# POWER.net
KiCad netlist of a schematic drawn in Altium Designer
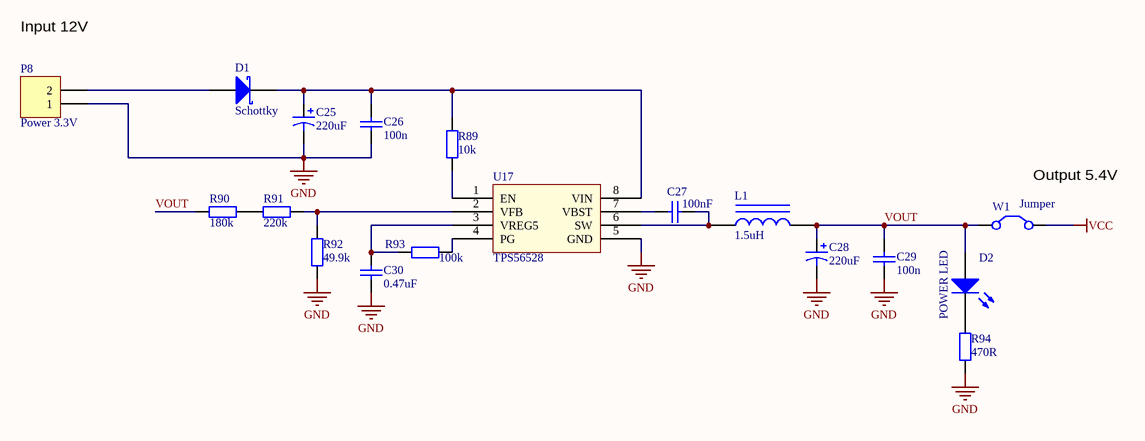
[diagram p0: POWER.SchDoc]

(export (version "E")
  (design (tool "Eeschema 10.0.6"))
  (components
    (comp (ref "C25")
      (value "220uF")
      (footprint "SMD CAPACITOR 220uF")
      (description "Capacitor")
      (fields (field (name "PUBLISHER") "Altium Limited"))
      (libsource (lib "Miscellaneous Devices") (part "Cap Pol1"))
    )
    (comp (ref "C26")
      (value "100n")
      (footprint "1608[0603]")
      (description "Capacitor")
      (fields (field (name "PUBLISHER") "Altium Limited"))
      (libsource (lib "Miscellaneous Devices") (part "Cap"))
    )
    (comp (ref "C27")
      (value "100nF")
      (footprint "1608[0603]")
      (description "Capacitor")
      (fields (field (name "PUBLISHER") "Altium Limited"))
      (libsource (lib "Miscellaneous Devices") (part "Cap"))
    )
    (comp (ref "C28")
      (value "220uF")
      (footprint "SMD CAPACITOR 220uF")
      (description "Capacitor")
      (fields (field (name "PUBLISHER") "Altium Limited"))
      (libsource (lib "Miscellaneous Devices") (part "Cap Pol1"))
    )
    (comp (ref "C29")
      (value "100n")
      (footprint "1608[0603]")
      (description "Capacitor")
      (fields (field (name "PUBLISHER") "Altium Limited"))
      (libsource (lib "Miscellaneous Devices") (part "Cap"))
    )
    (comp (ref "C30")
      (value "0.47uF")
      (footprint "1608[0603]")
      (description "Capacitor")
      (fields (field (name "PUBLISHER") "Altium Limited"))
      (libsource (lib "Miscellaneous Devices") (part "Cap"))
    )
    (comp (ref "D1")
      (value "Schottky")
      (footprint "SMB")
      (description "Schottky Diode")
      (fields (field (name "PUBLISHER") "Altium Limited"))
      (libsource (lib "Miscellaneous Devices") (part "D Schottky"))
    )
    (comp (ref "D2")
      (value "POWER LED")
      (footprint "LED-1")
      (description "Typical INFRARED GaAs LED")
      (fields (field (name "PUBLISHER") "Altium Limited"))
      (libsource (lib "Miscellaneous Devices") (part "LED0"))
    )
    (comp (ref "L1")
      (value "1.5uH")
      (footprint "LukaLIBRARY:Inductor")
      (description "Magnetic-Core Inductor")
      (fields (field (name "PUBLISHER") "Altium Limited"))
      (libsource (lib "Miscellaneous Devices") (part "Inductor Iron"))
    )
    (comp (ref "P8")
      (value "Power 3.3V")
      (footprint "Block2 - 3.81")
      (description "Header, 2-Pin")
      (fields (field (name "PUBLISHER") "Altium Limited"))
      (libsource (lib "Miscellaneous Connectors") (part "Header 2"))
    )
    (comp (ref "R89")
      (value "10k")
      (footprint "1608[0603]")
      (description "Resistor")
      (fields (field (name "PUBLISHER") "Altium Limited"))
      (libsource (lib "Miscellaneous Devices") (part "Res2"))
    )
    (comp (ref "R90")
      (value "180k")
      (footprint "6-0805_L")
      (description "Resistor")
      (fields (field (name "PUBLISHER") "Altium Limited"))
      (libsource (lib "") (part "Res2_1"))
    )
    (comp (ref "R91")
      (value "220k")
      (footprint "6-0805_L")
      (description "Resistor")
      (fields (field (name "PUBLISHER") "Altium Limited"))
      (libsource (lib "") (part "Res2_1"))
    )
    (comp (ref "R92")
      (value "49.9k")
      (footprint "1608[0603]")
      (description "Resistor")
      (fields (field (name "PUBLISHER") "Altium Limited"))
      (libsource (lib "Miscellaneous Devices") (part "Res2"))
    )
    (comp (ref "R93")
      (value "100k")
      (footprint "1608[0603]")
      (description "Resistor")
      (fields (field (name "PUBLISHER") "Altium Limited"))
      (libsource (lib "") (part "Res2_1"))
    )
    (comp (ref "R94")
      (value "470R")
      (footprint "1608[0603]")
      (description "Resistor")
      (fields (field (name "PUBLISHER") "Altium Limited"))
      (libsource (lib "Miscellaneous Devices") (part "Res2"))
    )
    (comp (ref "U17")
      (value "TPS56528")
      (footprint "TPS56528")
      (description "Step-Down Converter 5A 4.5V-18V")
      (libsource (lib "LP_Lib") (part "TPS56528"))
    )
    (comp (ref "W1")
      (value "Jumper")
      (footprint "HDR1X2")
      (description "Jumper Wire")
      (fields (field (name "PUBLISHER") "Altium Limited"))
      (libsource (lib "Miscellaneous Devices") (part "Jumper"))
    )
  )
  (nets
    (net (code "1") (name "/VOUT") (class "Default")
      (node (ref "C28") (pin "1") (pinfunction "1_1") (pintype "passive"))
      (node (ref "C29") (pin "1") (pinfunction "1_1") (pintype "passive"))
      (node (ref "D2") (pin "1") (pinfunction "A_1") (pintype "passive"))
      (node (ref "L1") (pin "2") (pinfunction "2_2") (pintype "passive"))
      (node (ref "R90") (pin "2") (pinfunction "2_2") (pintype "passive"))
      (node (ref "W1") (pin "1") (pinfunction "C1_1") (pintype "passive"))
    )
    (net (code "2") (name "GND") (class "Default")
      (node (ref "C25") (pin "2") (pinfunction "2_2") (pintype "passive"))
      (node (ref "C26") (pin "2") (pinfunction "2_2") (pintype "passive"))
      (node (ref "C28") (pin "2") (pinfunction "2_2") (pintype "passive"))
      (node (ref "C29") (pin "2") (pinfunction "2_2") (pintype "passive"))
      (node (ref "C30") (pin "2") (pinfunction "2_2") (pintype "passive"))
      (node (ref "P8") (pin "1") (pinfunction "1_1") (pintype "passive"))
      (node (ref "R92") (pin "1") (pinfunction "1_1") (pintype "passive"))
      (node (ref "R94") (pin "1") (pinfunction "1_1") (pintype "passive"))
      (node (ref "U17") (pin "5") (pinfunction "GND_5") (pintype "passive"))
    )
    (net (code "3") (name "Net-(D1-A)") (class "Default")
      (node (ref "D1") (pin "1") (pinfunction "A_1") (pintype "passive"))
      (node (ref "P8") (pin "2") (pinfunction "2_2") (pintype "passive"))
    )
    (net (code "4") (name "Net-(D1-K)") (class "Default")
      (node (ref "C25") (pin "1") (pinfunction "1_1") (pintype "passive"))
      (node (ref "C26") (pin "1") (pinfunction "1_1") (pintype "passive"))
      (node (ref "D1") (pin "2") (pinfunction "K_2") (pintype "passive"))
      (node (ref "R89") (pin "2") (pinfunction "2_2") (pintype "passive"))
      (node (ref "U17") (pin "8") (pinfunction "VIN_8") (pintype "passive"))
    )
    (net (code "5") (name "Net-(D2-K)") (class "Default")
      (node (ref "D2") (pin "2") (pinfunction "K_2") (pintype "passive"))
      (node (ref "R94") (pin "2") (pinfunction "2_2") (pintype "passive"))
    )
    (net (code "6") (name "Net-(R90-Pad1)") (class "Default")
      (node (ref "R90") (pin "1") (pinfunction "1_1") (pintype "passive"))
      (node (ref "R91") (pin "2") (pinfunction "2_2") (pintype "passive"))
    )
    (net (code "7") (name "Net-(U17-EN)") (class "Default")
      (node (ref "R89") (pin "1") (pinfunction "1_1") (pintype "passive"))
      (node (ref "U17") (pin "1") (pinfunction "EN_1") (pintype "passive"))
    )
    (net (code "8") (name "Net-(U17-PG)") (class "Default")
      (node (ref "R93") (pin "1") (pinfunction "1_1") (pintype "passive"))
      (node (ref "U17") (pin "4") (pinfunction "PG_4") (pintype "passive"))
    )
    (net (code "9") (name "Net-(U17-SW)") (class "Default")
      (node (ref "C27") (pin "2") (pinfunction "2_2") (pintype "passive"))
      (node (ref "L1") (pin "1") (pinfunction "1_1") (pintype "passive"))
      (node (ref "U17") (pin "6") (pinfunction "SW_6") (pintype "passive"))
    )
    (net (code "10") (name "Net-(U17-VBST)") (class "Default")
      (node (ref "C27") (pin "1") (pinfunction "1_1") (pintype "passive"))
      (node (ref "U17") (pin "7") (pinfunction "VBST_7") (pintype "passive"))
    )
    (net (code "11") (name "Net-(U17-VFB)") (class "Default")
      (node (ref "R91") (pin "1") (pinfunction "1_1") (pintype "passive"))
      (node (ref "R92") (pin "2") (pinfunction "2_2") (pintype "passive"))
      (node (ref "U17") (pin "2") (pinfunction "VFB_2") (pintype "passive"))
    )
    (net (code "12") (name "Net-(U17-VREG5)") (class "Default")
      (node (ref "C30") (pin "1") (pinfunction "1_1") (pintype "passive"))
      (node (ref "R93") (pin "2") (pinfunction "2_2") (pintype "passive"))
      (node (ref "U17") (pin "3") (pinfunction "VREG5_3") (pintype "passive"))
    )
    (net (code "13") (name "VCC") (class "Default")
      (node (ref "W1") (pin "2") (pinfunction "C2_2") (pintype "passive"))
    )
  )
)
